# eCog115_PS2.net
KiCad netlist of a schematic drawn in EAGLE
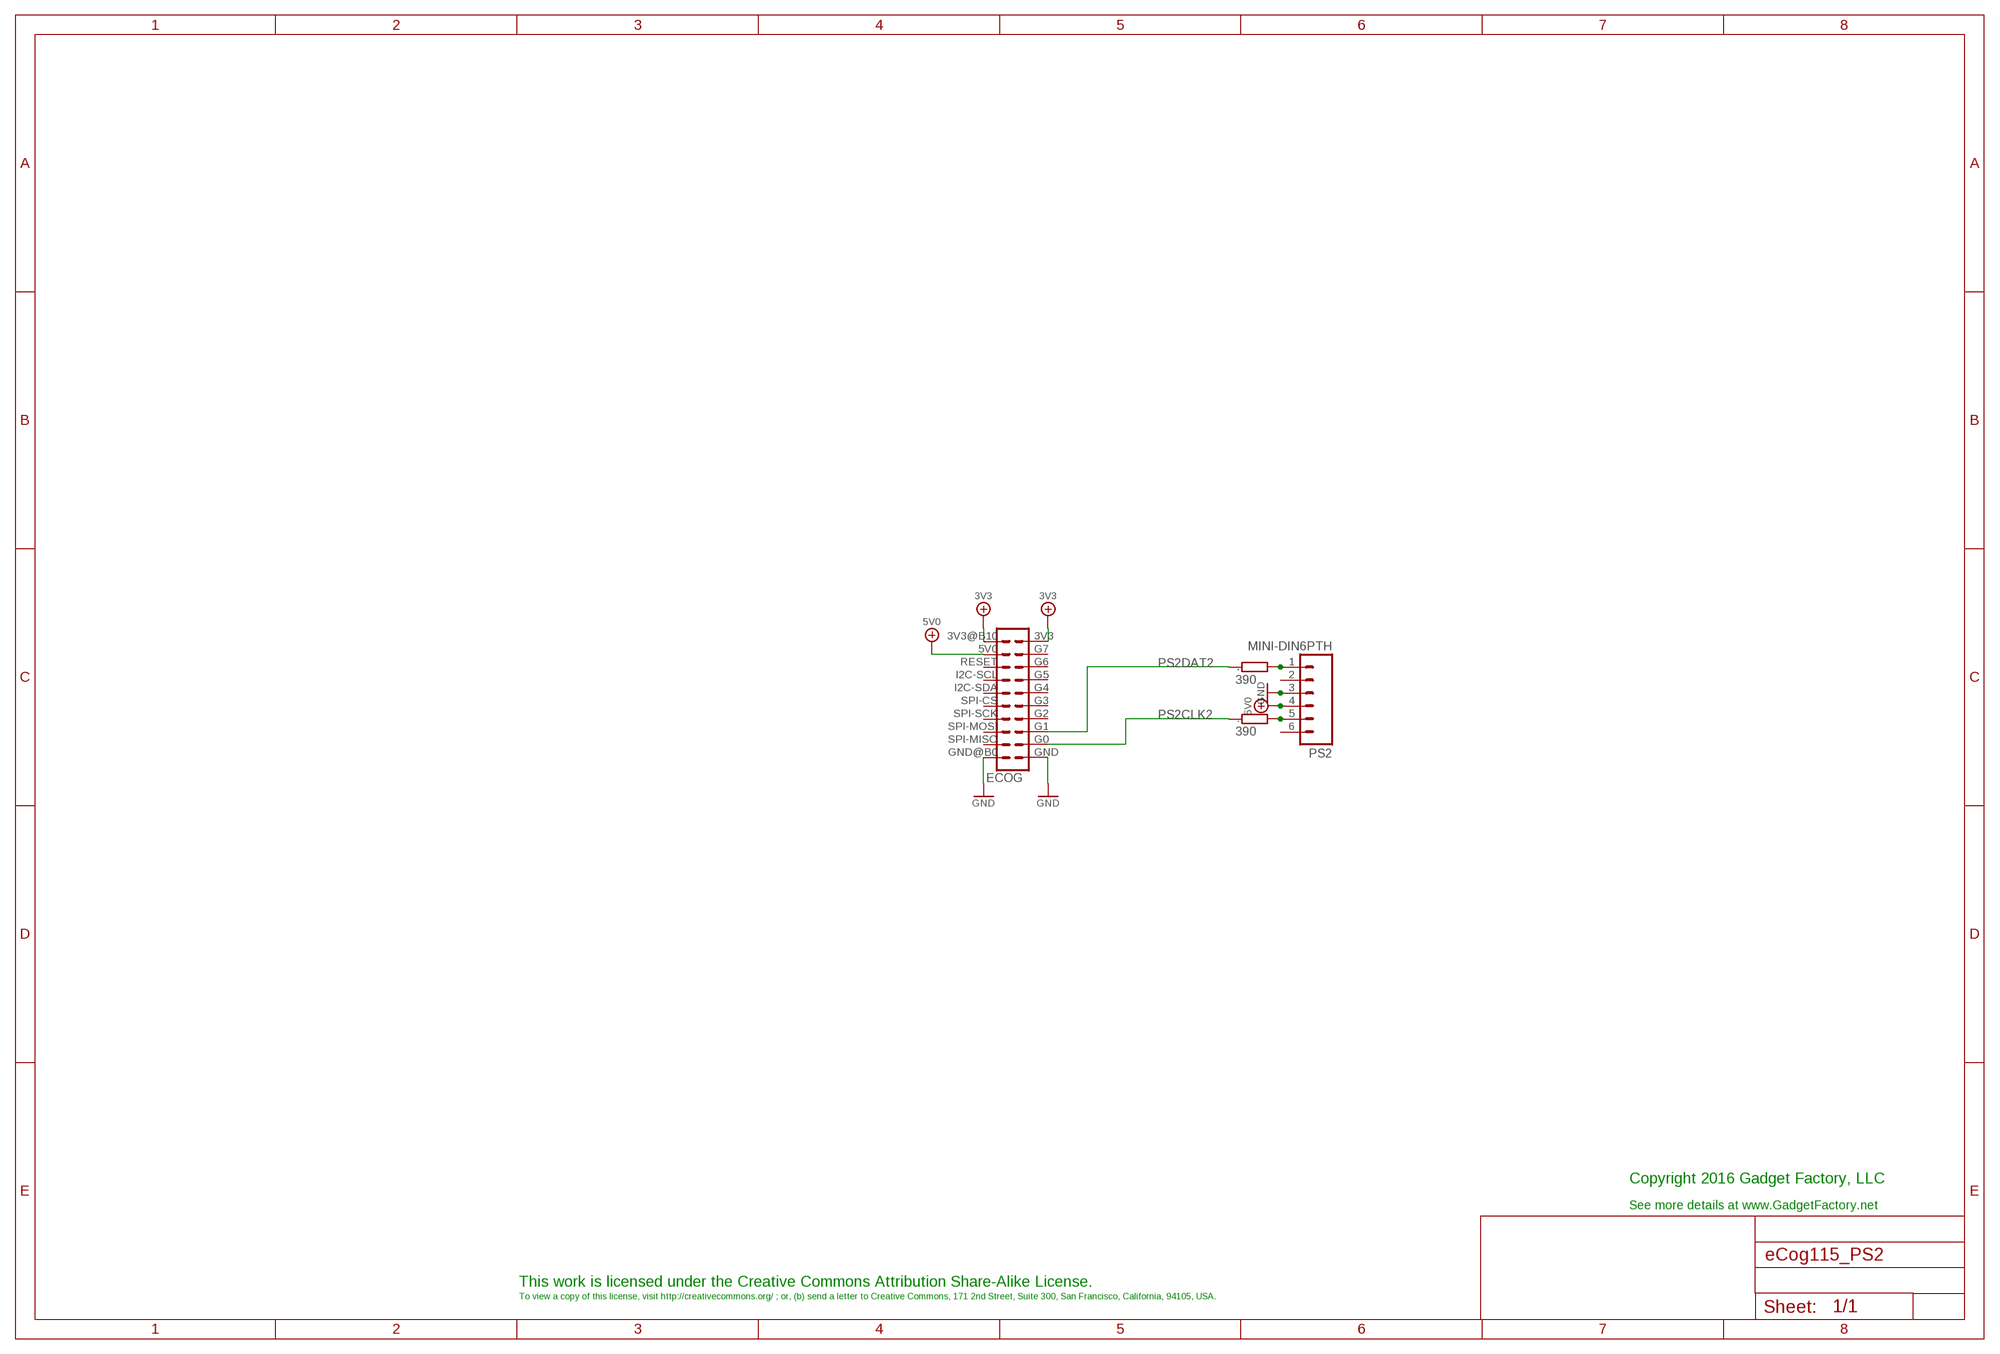
[diagram p0: schematic, sheet 1]

(export (version "E")
  (design (tool "Eeschema 10.0.6"))
  (components
    (comp (ref "ECOG")
      (value "ECOG_DUALTHROUGHHOLE")
      (footprint "eagle-import:ECOG_DUAL_TH")
      (libsource (lib "eagle-import") (part "ECOG_DUALTHROUGHHOLE"))
    )
    (comp (ref "PS2")
      (value "MINI-DIN6PTH")
      (footprint "eagle-import:MINI-DIN6")
      (libsource (lib "eagle-import") (part "MINI-DIN6PTH"))
    )
    (comp (ref "R1")
      (value "390")
      (footprint "eagle-import:0603")
      (libsource (lib "eagle-import") (part "R0603"))
    )
    (comp (ref "R2")
      (value "390")
      (footprint "eagle-import:0603")
      (libsource (lib "eagle-import") (part "R0603"))
    )
  )
  (nets
    (net (code "1") (name "/PS2CLK2") (class "Default")
      (node (ref "ECOG") (pin "G0") (pinfunction "G0_G0") (pintype "passive"))
      (node (ref "R2") (pin "1") (pinfunction "1_1") (pintype "passive"))
    )
    (net (code "2") (name "/PS2DAT2") (class "Default")
      (node (ref "ECOG") (pin "G1") (pinfunction "G1_G1") (pintype "passive"))
      (node (ref "R1") (pin "1") (pinfunction "1_1") (pintype "passive"))
    )
    (net (code "3") (name "3V3") (class "Default")
      (node (ref "ECOG") (pin "3V3") (pinfunction "3V3_3V3") (pintype "passive"))
      (node (ref "ECOG") (pin "3V3@B10") (pinfunction "3V3_3V3@B10") (pintype "passive"))
    )
    (net (code "4") (name "5V0") (class "Default")
      (node (ref "ECOG") (pin "5V0") (pinfunction "5V_5V0") (pintype "passive"))
      (node (ref "PS2") (pin "4") (pinfunction "4_4") (pintype "passive"))
    )
    (net (code "5") (name "GND") (class "Default")
      (node (ref "ECOG") (pin "GND") (pinfunction "GND_GND") (pintype "passive"))
      (node (ref "ECOG") (pin "GND@B0") (pinfunction "GND_GND@B0") (pintype "passive"))
      (node (ref "PS2") (pin "3") (pinfunction "3_3") (pintype "passive"))
    )
    (net (code "6") (name "Net-(PS2-Pad1)") (class "Default")
      (node (ref "PS2") (pin "1") (pinfunction "1_1") (pintype "passive"))
      (node (ref "R1") (pin "2") (pinfunction "2_2") (pintype "passive"))
    )
    (net (code "7") (name "Net-(PS2-Pad5)") (class "Default")
      (node (ref "PS2") (pin "5") (pinfunction "5_5") (pintype "passive"))
      (node (ref "R2") (pin "2") (pinfunction "2_2") (pintype "passive"))
    )
    (net (code "8") (name "unconnected-(ECOG-PadG2)") (class "Default")
      (node (ref "ECOG") (pin "G2") (pinfunction "G2_G2") (pintype "passive"))
    )
    (net (code "9") (name "unconnected-(ECOG-PadG3)") (class "Default")
      (node (ref "ECOG") (pin "G3") (pinfunction "G3_G3") (pintype "passive"))
    )
    (net (code "10") (name "unconnected-(ECOG-PadG4)") (class "Default")
      (node (ref "ECOG") (pin "G4") (pinfunction "G4_G4") (pintype "passive"))
    )
    (net (code "11") (name "unconnected-(ECOG-PadG5)") (class "Default")
      (node (ref "ECOG") (pin "G5") (pinfunction "G5_G5") (pintype "passive"))
    )
    (net (code "12") (name "unconnected-(ECOG-PadG6)") (class "Default")
      (node (ref "ECOG") (pin "G6") (pinfunction "G6_G6") (pintype "passive"))
    )
    (net (code "13") (name "unconnected-(ECOG-PadG7)") (class "Default")
      (node (ref "ECOG") (pin "G7") (pinfunction "G7_G7") (pintype "passive"))
    )
    (net (code "14") (name "unconnected-(ECOG-PadI2C-SCL)") (class "Default")
      (node (ref "ECOG") (pin "I2C-SCL") (pinfunction "I2C-SCL_I2C-SCL") (pintype "passive"))
    )
    (net (code "15") (name "unconnected-(ECOG-PadI2C-SDA)") (class "Default")
      (node (ref "ECOG") (pin "I2C-SDA") (pinfunction "I2C-SDA_I2C-SDA") (pintype "passive"))
    )
    (net (code "16") (name "unconnected-(ECOG-PadRESET)") (class "Default")
      (node (ref "ECOG") (pin "RESET") (pinfunction "RESET_RESET") (pintype "passive"))
    )
    (net (code "17") (name "unconnected-(ECOG-PadSPI-CS)") (class "Default")
      (node (ref "ECOG") (pin "SPI-CS") (pinfunction "SPI-CS_SPI-CS") (pintype "passive"))
    )
    (net (code "18") (name "unconnected-(ECOG-PadSPI-MISO)") (class "Default")
      (node (ref "ECOG") (pin "SPI-MISO") (pinfunction "SPI-MISO_SPI-MISO") (pintype "passive"))
    )
    (net (code "19") (name "unconnected-(ECOG-PadSPI-MOSI)") (class "Default")
      (node (ref "ECOG") (pin "SPI-MOSI") (pinfunction "SPI-MOSI_SPI-MOSI") (pintype "passive"))
    )
    (net (code "20") (name "unconnected-(ECOG-PadSPI-SCK)") (class "Default")
      (node (ref "ECOG") (pin "SPI-SCK") (pinfunction "SPI-SCK_SPI-SCK") (pintype "passive"))
    )
    (net (code "21") (name "unconnected-(PS2-Pad2)") (class "Default")
      (node (ref "PS2") (pin "2") (pinfunction "2_2") (pintype "passive"))
    )
    (net (code "22") (name "unconnected-(PS2-Pad6)") (class "Default")
      (node (ref "PS2") (pin "6") (pinfunction "6_6") (pintype "passive"))
    )
  )
)
